# ProPrj_OASman_SMD_test_board_2_2025-03-0.net
KiCad netlist of a schematic drawn in EasyEDA Pro
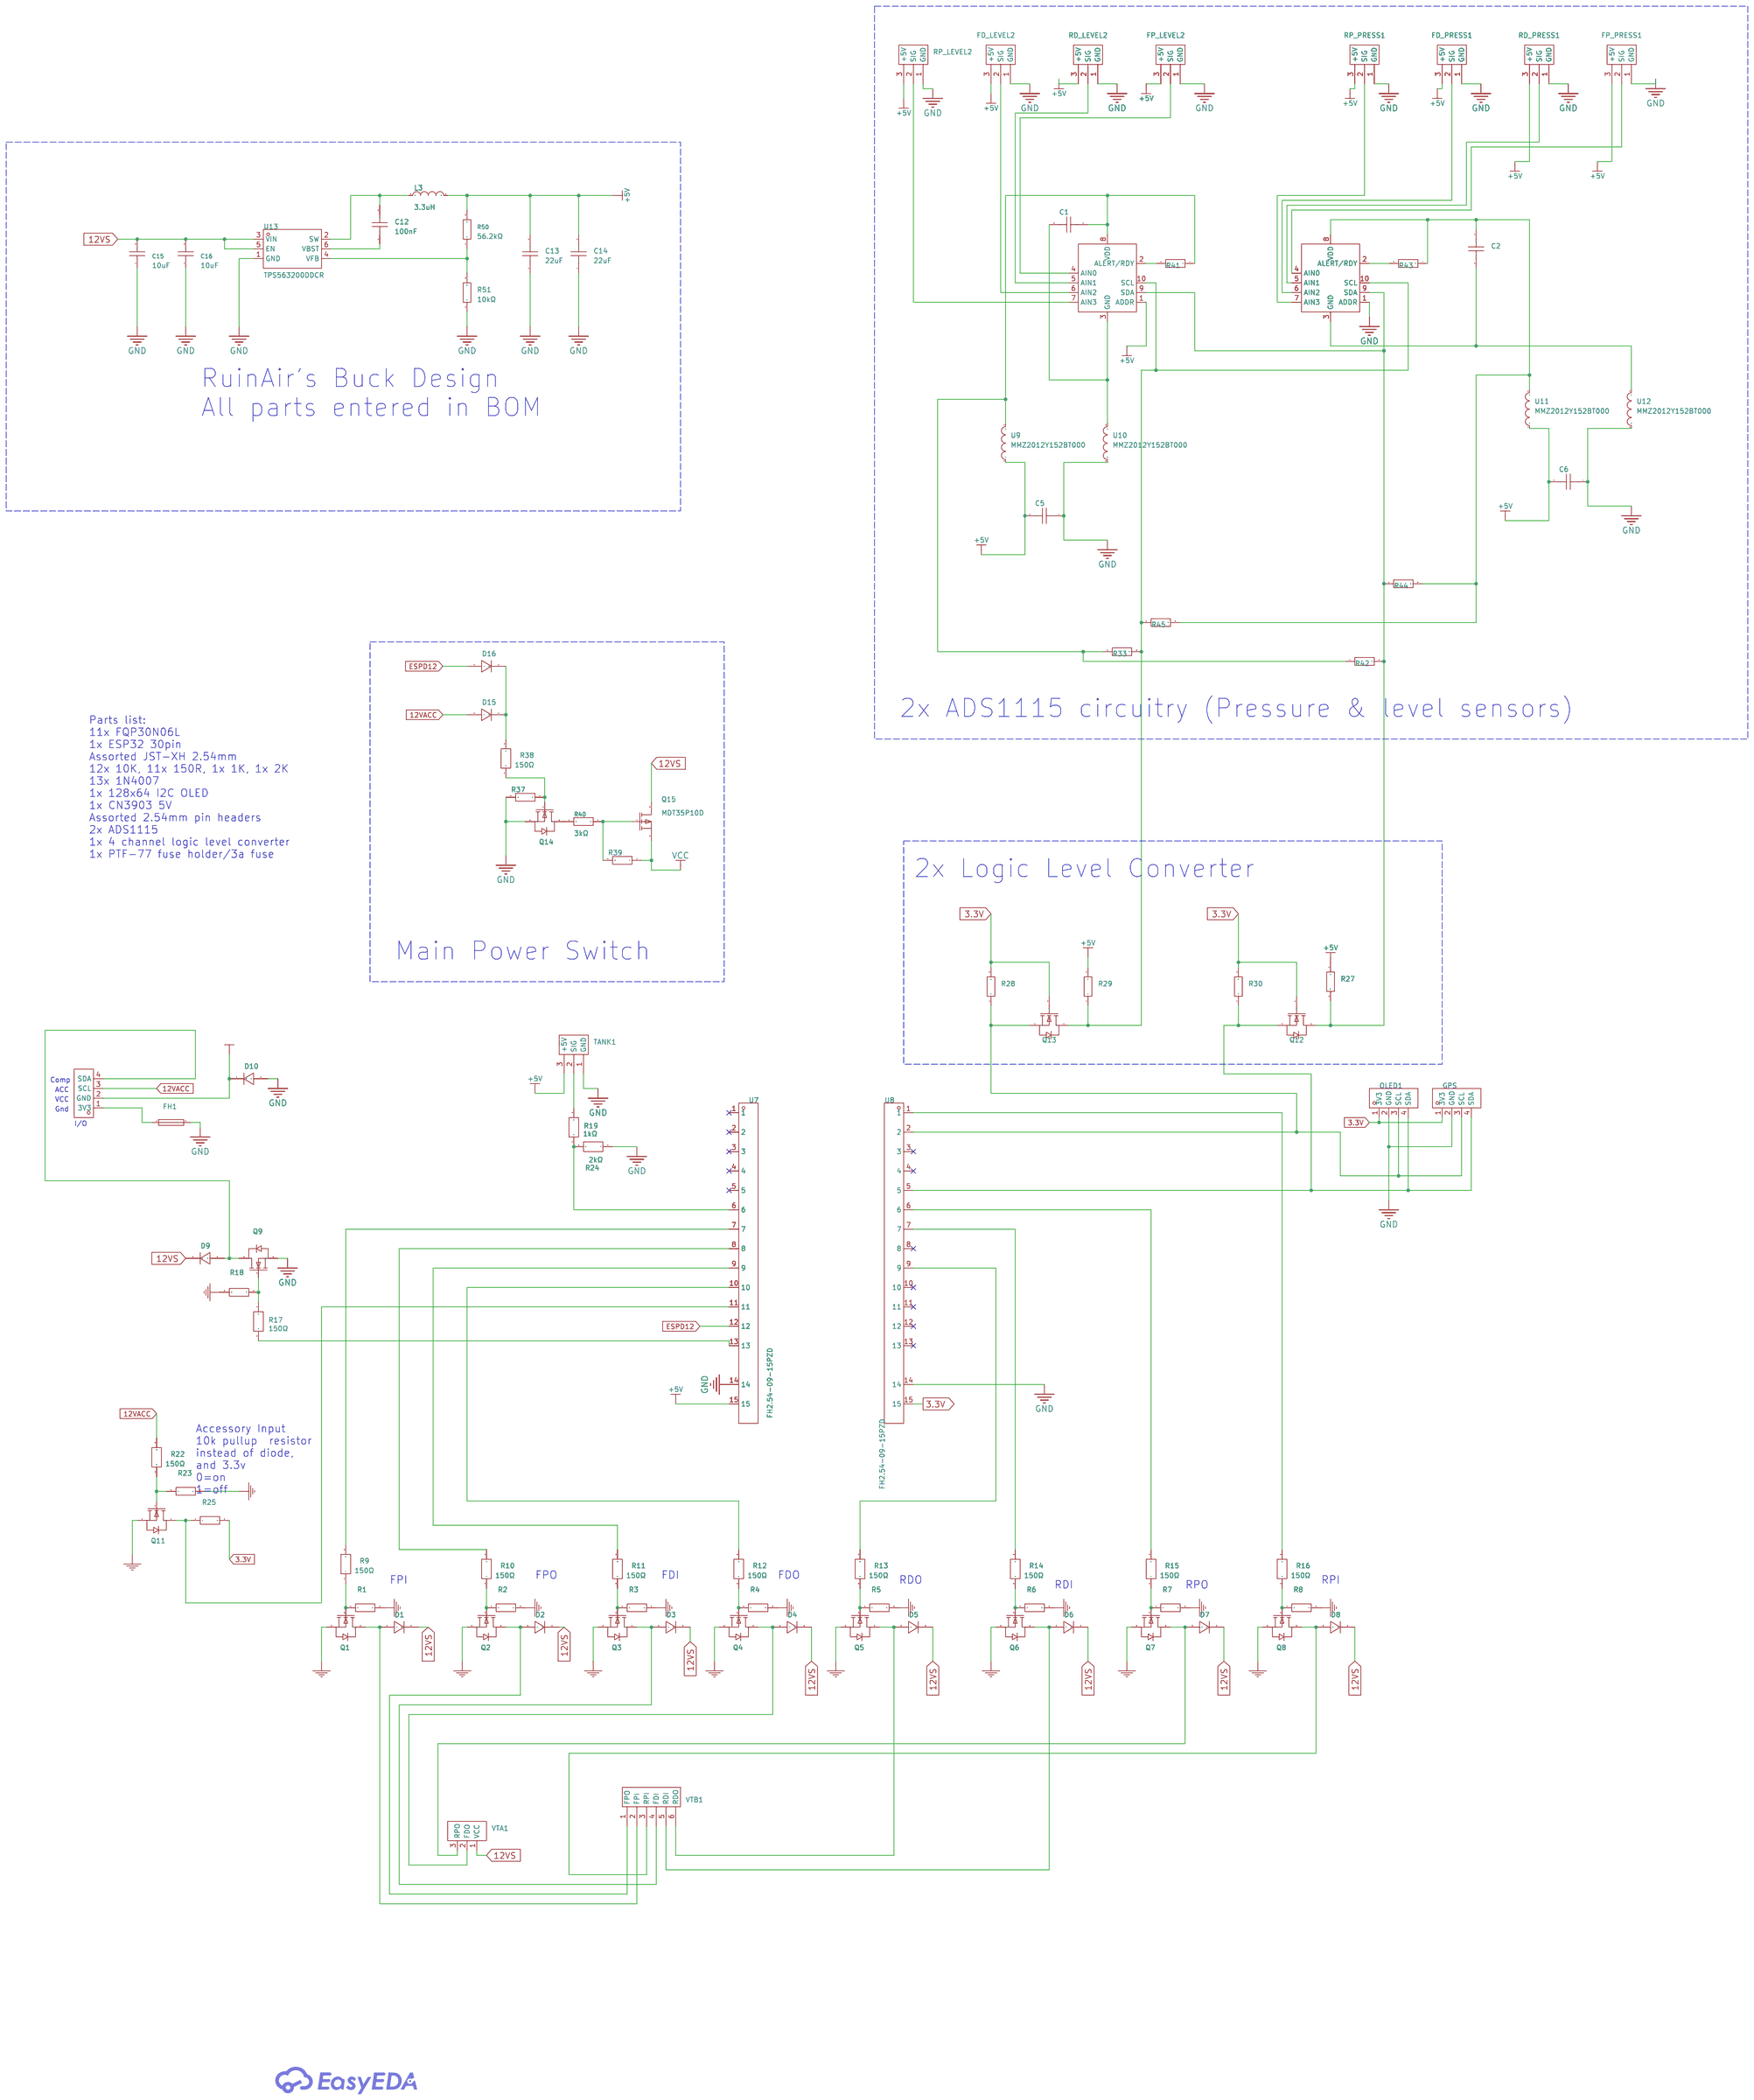
[diagram p0: schematic sheet]

(export (version "E")
  (design (tool "Eeschema 10.0.6"))
  (components
    (comp (ref "C1")
      (value "1uF")
      (footprint "easyedapro:C0603")
      (fields
        (field (name "Manufacturer Part") "GRM188R61H105KAALD")
        (field (name "Manufacturer") "muRata(村田)")
      )
      (libsource (lib "easyedapro") (part "GRM188R61H105KAALD"))
    )
    (comp (ref "C2")
      (value "1uF")
      (footprint "easyedapro:C0603")
      (fields
        (field (name "Manufacturer Part") "GRM188R61H105KAALD")
        (field (name "Manufacturer") "muRata(村田)")
      )
      (libsource (lib "easyedapro") (part "GRM188R61H105KAALD"))
    )
    (comp (ref "C5")
      (value "1uF")
      (footprint "easyedapro:C0603")
      (fields
        (field (name "Manufacturer Part") "GRM188R61H105KAALD")
        (field (name "Manufacturer") "muRata(村田)")
      )
      (libsource (lib "easyedapro") (part "GRM188R61H105KAALD"))
    )
    (comp (ref "C6")
      (value "1uF")
      (footprint "easyedapro:C0603")
      (fields
        (field (name "Manufacturer Part") "GRM188R61H105KAALD")
        (field (name "Manufacturer") "muRata(村田)")
      )
      (libsource (lib "easyedapro") (part "GRM188R61H105KAALD"))
    )
    (comp (ref "C12")
      (value "100nF")
      (footprint "easyedapro:C0402")
      (fields
        (field (name "Manufacturer Part") "CL05B104KB54PNC")
        (field (name "Manufacturer") "SAMSUNG(三星)")
      )
      (libsource (lib "easyedapro") (part "CL05B104KB54PNC"))
    )
    (comp (ref "C13")
      (value "22uF")
      (footprint "easyedapro:C0805")
      (fields
        (field (name "Manufacturer Part") "CL21A226MAQNNNE")
        (field (name "Manufacturer") "SAMSUNG(三星)")
      )
      (libsource (lib "easyedapro") (part "CL21A226MAQNNNE"))
    )
    (comp (ref "C14")
      (value "22uF")
      (footprint "easyedapro:C0805")
      (fields
        (field (name "Manufacturer Part") "CL21A226MAQNNNE")
        (field (name "Manufacturer") "SAMSUNG(三星)")
      )
      (libsource (lib "easyedapro") (part "CL21A226MAQNNNE"))
    )
    (comp (ref "C15")
      (value "10uF")
      (footprint "easyedapro:C1206")
      (fields
        (field (name "Manufacturer Part") "CL31A106KBHNNNE")
        (field (name "Manufacturer") "SAMSUNG(三星)")
      )
      (libsource (lib "easyedapro") (part "CL31A106KBHNNNE"))
    )
    (comp (ref "C16")
      (value "10uF")
      (footprint "easyedapro:C1206")
      (fields
        (field (name "Manufacturer Part") "CL31A106KBHNNNE")
        (field (name "Manufacturer") "SAMSUNG(三星)")
      )
      (libsource (lib "easyedapro") (part "CL31A106KBHNNNE"))
    )
    (comp (ref "CN1")
      (value "XH-4A绿色")
      (footprint "easyedapro:CONN-TH_XH-4A-1")
      (fields (field (name "Manufacturer") "BOOMELE(博穆精密)"))
      (libsource (lib "easyedapro") (part "XH-4A绿色"))
    )
    (comp (ref "D1")
      (value "SM4007PL")
      (footprint "easyedapro:SOD-123F_L2.8-W1.8-LS3.7-RD")
      (fields (field (name "Manufacturer") "MDD(辰达半导体)"))
      (libsource (lib "easyedapro") (part "SM4007PL"))
    )
    (comp (ref "D2")
      (value "SM4007PL")
      (footprint "easyedapro:SOD-123F_L2.8-W1.8-LS3.7-RD")
      (fields (field (name "Manufacturer") "MDD(辰达半导体)"))
      (libsource (lib "easyedapro") (part "SM4007PL"))
    )
    (comp (ref "D3")
      (value "SM4007PL")
      (footprint "easyedapro:SOD-123F_L2.8-W1.8-LS3.7-RD")
      (fields (field (name "Manufacturer") "MDD(辰达半导体)"))
      (libsource (lib "easyedapro") (part "SM4007PL"))
    )
    (comp (ref "D4")
      (value "SM4007PL")
      (footprint "easyedapro:SOD-123F_L2.8-W1.8-LS3.7-RD")
      (fields (field (name "Manufacturer") "MDD(辰达半导体)"))
      (libsource (lib "easyedapro") (part "SM4007PL"))
    )
    (comp (ref "D5")
      (value "SM4007PL")
      (footprint "easyedapro:SOD-123F_L2.8-W1.8-LS3.7-RD")
      (fields (field (name "Manufacturer") "MDD(辰达半导体)"))
      (libsource (lib "easyedapro") (part "SM4007PL"))
    )
    (comp (ref "D6")
      (value "SM4007PL")
      (footprint "easyedapro:SOD-123F_L2.8-W1.8-LS3.7-RD")
      (fields (field (name "Manufacturer") "MDD(辰达半导体)"))
      (libsource (lib "easyedapro") (part "SM4007PL"))
    )
    (comp (ref "D7")
      (value "SM4007PL")
      (footprint "easyedapro:SOD-123F_L2.8-W1.8-LS3.7-RD")
      (fields (field (name "Manufacturer") "MDD(辰达半导体)"))
      (libsource (lib "easyedapro") (part "SM4007PL"))
    )
    (comp (ref "D8")
      (value "SM4007PL")
      (footprint "easyedapro:SOD-123F_L2.8-W1.8-LS3.7-RD")
      (fields (field (name "Manufacturer") "MDD(辰达半导体)"))
      (libsource (lib "easyedapro") (part "SM4007PL"))
    )
    (comp (ref "D9")
      (value "SM4007PL")
      (footprint "easyedapro:SOD-123F_L2.8-W1.8-LS3.7-RD")
      (fields (field (name "Manufacturer") "MDD(辰达半导体)"))
      (libsource (lib "easyedapro") (part "SM4007PL"))
    )
    (comp (ref "D10")
      (value "SM4007PL")
      (footprint "easyedapro:SOD-123F_L2.8-W1.8-LS3.7-RD")
      (fields (field (name "Manufacturer") "MDD(辰达半导体)"))
      (libsource (lib "easyedapro") (part "SM4007PL"))
    )
    (comp (ref "D15")
      (value "SM4007PL")
      (footprint "easyedapro:SOD-123F_L2.8-W1.8-LS3.7-RD")
      (fields (field (name "Manufacturer") "MDD(辰达半导体)"))
      (libsource (lib "easyedapro") (part "SM4007PL"))
    )
    (comp (ref "D16")
      (value "SM4007PL")
      (footprint "easyedapro:SOD-123F_L2.8-W1.8-LS3.7-RD")
      (fields (field (name "Manufacturer") "MDD(辰达半导体)"))
      (libsource (lib "easyedapro") (part "SM4007PL"))
    )
    (comp (ref "FD_LEVEL2")
      (value "XH-3A")
      (footprint "easyedapro:CONN-TH_XH-3A")
      (fields (field (name "Manufacturer") "BOOMELE(博穆精密)"))
      (libsource (lib "easyedapro") (part "XH-3A"))
    )
    (comp (ref "FD_PRESS1")
      (value "XH-3A")
      (footprint "easyedapro:CONN-TH_XH-3A")
      (fields (field (name "Manufacturer") "BOOMELE(博穆精密)"))
      (libsource (lib "easyedapro") (part "XH-3A"))
    )
    (comp (ref "FH1")
      (value "PTF-77")
      (description "Fuseholder Type:- Voltage Rating:250V Current Rating:10A Fuse Type:- Fuse Size:-")
      (libsource (lib "easyedapro") (part "PTF-77"))
    )
    (comp (ref "FP_LEVEL2")
      (value "XH-3A")
      (footprint "easyedapro:CONN-TH_XH-3A")
      (fields (field (name "Manufacturer") "BOOMELE(博穆精密)"))
      (libsource (lib "easyedapro") (part "XH-3A"))
    )
    (comp (ref "FP_PRESS1")
      (value "XH-3A")
      (footprint "easyedapro:CONN-TH_XH-3A")
      (fields (field (name "Manufacturer") "BOOMELE(博穆精密)"))
      (libsource (lib "easyedapro") (part "XH-3A"))
    )
    (comp (ref "GPS")
      (value "XH-4A绿色")
      (footprint "easyedapro:CONN-TH_XH-4A-1")
      (fields (field (name "Manufacturer") "BOOMELE(博穆精密)"))
      (libsource (lib "easyedapro") (part "XH-4A绿色"))
    )
    (comp (ref "L3")
      (value "3.3uH")
      (footprint "easyedapro:IND-SMD_L4.5-W4.1_SL0420")
      (description "Inductance: Tolerance:±20% Tolerance:±20% Rated Current: Saturation Current (Isat):4A")
      (fields (field (name "Manufacturer Part") "SL0420-3R3M") (field (name "Manufacturer") "台湾陆海"))
      (libsource (lib "easyedapro") (part "SL0420-3R3M"))
    )
    (comp (ref "OLED1")
      (value "XH-4A绿色")
      (footprint "easyedapro:CONN-TH_XH-4A-1")
      (fields (field (name "Manufacturer") "BOOMELE(博穆精密)"))
      (libsource (lib "easyedapro") (part "XH-4A绿色"))
    )
    (comp (ref "Q1") (value "MDT30N06L") (libsource (lib "easyedapro") (part "FQP30N06L")))
    (comp (ref "Q2") (value "MDT30N06L") (libsource (lib "easyedapro") (part "FQP30N06L")))
    (comp (ref "Q3") (value "MDT30N06L") (libsource (lib "easyedapro") (part "FQP30N06L")))
    (comp (ref "Q4") (value "MDT30N06L") (libsource (lib "easyedapro") (part "FQP30N06L")))
    (comp (ref "Q5") (value "MDT30N06L") (libsource (lib "easyedapro") (part "FQP30N06L")))
    (comp (ref "Q6") (value "MDT30N06L") (libsource (lib "easyedapro") (part "FQP30N06L")))
    (comp (ref "Q7") (value "MDT30N06L") (libsource (lib "easyedapro") (part "FQP30N06L")))
    (comp (ref "Q8") (value "MDT30N06L") (libsource (lib "easyedapro") (part "FQP30N06L")))
    (comp (ref "Q9") (value "MDT30N06L") (libsource (lib "easyedapro") (part "FQP30N06L")))
    (comp (ref "Q11") (value "MDT30N06L") (libsource (lib "easyedapro") (part "FQP30N06L")))
    (comp (ref "Q12")
      (value "BSS138")
      (footprint "easyedapro:SOT-23-3_L2.9-W1.6-P1.90-LS2.8-BR")
      (fields (field (name "Manufacturer") "SHIKUES(时科)"))
      (libsource (lib "easyedapro") (part "BSS138_C112239"))
    )
    (comp (ref "Q13")
      (value "BSS138")
      (footprint "easyedapro:SOT-23-3_L2.9-W1.6-P1.90-LS2.8-BR")
      (fields (field (name "Manufacturer") "SHIKUES(时科)"))
      (libsource (lib "easyedapro") (part "BSS138_C112239"))
    )
    (comp (ref "Q14") (value "MDT30N06L") (libsource (lib "easyedapro") (part "FQP30N06L")))
    (comp (ref "Q15")
      (value "MDT35P10D")
      (footprint "easyedapro:TO-252-2_L6.6-W6.1-P4.57-LS9.9-BR-CW")
      (fields (field (name "Manufacturer") "minos(迈诺斯)"))
      (libsource (lib "easyedapro") (part "MDT35P10D"))
    )
    (comp (ref "R1")
      (value "10kΩ")
      (footprint "easyedapro:R1206")
      (fields
        (field (name "Manufacturer Part") "1206W4F1002T5E")
        (field (name "Manufacturer") "UNI-ROYAL(厚声)")
      )
      (libsource (lib "easyedapro") (part "1206W4F1002T5E"))
    )
    (comp (ref "R2")
      (value "10kΩ")
      (footprint "easyedapro:R1206")
      (fields
        (field (name "Manufacturer Part") "1206W4F1002T5E")
        (field (name "Manufacturer") "UNI-ROYAL(厚声)")
      )
      (libsource (lib "easyedapro") (part "1206W4F1002T5E"))
    )
    (comp (ref "R3")
      (value "10kΩ")
      (footprint "easyedapro:R1206")
      (fields
        (field (name "Manufacturer Part") "1206W4F1002T5E")
        (field (name "Manufacturer") "UNI-ROYAL(厚声)")
      )
      (libsource (lib "easyedapro") (part "1206W4F1002T5E"))
    )
    (comp (ref "R4")
      (value "10kΩ")
      (footprint "easyedapro:R1206")
      (fields
        (field (name "Manufacturer Part") "1206W4F1002T5E")
        (field (name "Manufacturer") "UNI-ROYAL(厚声)")
      )
      (libsource (lib "easyedapro") (part "1206W4F1002T5E"))
    )
    (comp (ref "R5")
      (value "10kΩ")
      (footprint "easyedapro:R1206")
      (fields
        (field (name "Manufacturer Part") "1206W4F1002T5E")
        (field (name "Manufacturer") "UNI-ROYAL(厚声)")
      )
      (libsource (lib "easyedapro") (part "1206W4F1002T5E"))
    )
    (comp (ref "R6")
      (value "10kΩ")
      (footprint "easyedapro:R1206")
      (fields
        (field (name "Manufacturer Part") "1206W4F1002T5E")
        (field (name "Manufacturer") "UNI-ROYAL(厚声)")
      )
      (libsource (lib "easyedapro") (part "1206W4F1002T5E"))
    )
    (comp (ref "R7")
      (value "10kΩ")
      (footprint "easyedapro:R1206")
      (fields
        (field (name "Manufacturer Part") "1206W4F1002T5E")
        (field (name "Manufacturer") "UNI-ROYAL(厚声)")
      )
      (libsource (lib "easyedapro") (part "1206W4F1002T5E"))
    )
    (comp (ref "R8")
      (value "10kΩ")
      (footprint "easyedapro:R1206")
      (fields
        (field (name "Manufacturer Part") "1206W4F1002T5E")
        (field (name "Manufacturer") "UNI-ROYAL(厚声)")
      )
      (libsource (lib "easyedapro") (part "1206W4F1002T5E"))
    )
    (comp (ref "R9")
      (value "150Ω")
      (footprint "easyedapro:R1206")
      (fields (field (name "Manufacturer Part") "FRC1206J151 TS") (field (name "Manufacturer") "FOJAN(富捷)"))
      (libsource (lib "easyedapro") (part "FRC1206J151 TS"))
    )
    (comp (ref "R10")
      (value "150Ω")
      (footprint "easyedapro:R1206")
      (fields (field (name "Manufacturer Part") "FRC1206J151 TS") (field (name "Manufacturer") "FOJAN(富捷)"))
      (libsource (lib "easyedapro") (part "FRC1206J151 TS"))
    )
    (comp (ref "R11")
      (value "150Ω")
      (footprint "easyedapro:R1206")
      (fields (field (name "Manufacturer Part") "FRC1206J151 TS") (field (name "Manufacturer") "FOJAN(富捷)"))
      (libsource (lib "easyedapro") (part "FRC1206J151 TS"))
    )
    (comp (ref "R12")
      (value "150Ω")
      (footprint "easyedapro:R1206")
      (fields (field (name "Manufacturer Part") "FRC1206J151 TS") (field (name "Manufacturer") "FOJAN(富捷)"))
      (libsource (lib "easyedapro") (part "FRC1206J151 TS"))
    )
    (comp (ref "R13")
      (value "150Ω")
      (footprint "easyedapro:R1206")
      (fields (field (name "Manufacturer Part") "FRC1206J151 TS") (field (name "Manufacturer") "FOJAN(富捷)"))
      (libsource (lib "easyedapro") (part "FRC1206J151 TS"))
    )
    (comp (ref "R14")
      (value "150Ω")
      (footprint "easyedapro:R1206")
      (fields (field (name "Manufacturer Part") "FRC1206J151 TS") (field (name "Manufacturer") "FOJAN(富捷)"))
      (libsource (lib "easyedapro") (part "FRC1206J151 TS"))
    )
    (comp (ref "R15")
      (value "150Ω")
      (footprint "easyedapro:R1206")
      (fields (field (name "Manufacturer Part") "FRC1206J151 TS") (field (name "Manufacturer") "FOJAN(富捷)"))
      (libsource (lib "easyedapro") (part "FRC1206J151 TS"))
    )
    (comp (ref "R16")
      (value "150Ω")
      (footprint "easyedapro:R1206")
      (fields (field (name "Manufacturer Part") "FRC1206J151 TS") (field (name "Manufacturer") "FOJAN(富捷)"))
      (libsource (lib "easyedapro") (part "FRC1206J151 TS"))
    )
    (comp (ref "R17")
      (value "150Ω")
      (footprint "easyedapro:R1206")
      (fields (field (name "Manufacturer Part") "FRC1206J151 TS") (field (name "Manufacturer") "FOJAN(富捷)"))
      (libsource (lib "easyedapro") (part "FRC1206J151 TS"))
    )
    (comp (ref "R18")
      (value "10kΩ")
      (footprint "easyedapro:R1206")
      (fields
        (field (name "Manufacturer Part") "1206W4F1002T5E")
        (field (name "Manufacturer") "UNI-ROYAL(厚声)")
      )
      (libsource (lib "easyedapro") (part "1206W4F1002T5E"))
    )
    (comp (ref "R19")
      (value "1kΩ")
      (footprint "easyedapro:R1206")
      (fields (field (name "Manufacturer Part") "FRC1206J102 TS") (field (name "Manufacturer") "FOJAN(富捷)"))
      (libsource (lib "easyedapro") (part "FRC1206J102 TS"))
    )
    (comp (ref "R22")
      (value "150Ω")
      (footprint "easyedapro:R1206")
      (fields (field (name "Manufacturer Part") "FRC1206J151 TS") (field (name "Manufacturer") "FOJAN(富捷)"))
      (libsource (lib "easyedapro") (part "FRC1206J151 TS"))
    )
    (comp (ref "R23")
      (value "10kΩ")
      (footprint "easyedapro:R1206")
      (fields
        (field (name "Manufacturer Part") "1206W4F1002T5E")
        (field (name "Manufacturer") "UNI-ROYAL(厚声)")
      )
      (libsource (lib "easyedapro") (part "1206W4F1002T5E"))
    )
    (comp (ref "R24")
      (value "2kΩ")
      (footprint "easyedapro:R1206")
      (fields (field (name "Manufacturer Part") "FRC1206J202 TS") (field (name "Manufacturer") "FOJAN(富捷)"))
      (libsource (lib "easyedapro") (part "FRC1206J202 TS"))
    )
    (comp (ref "R25")
      (value "10kΩ")
      (footprint "easyedapro:R1206")
      (fields
        (field (name "Manufacturer Part") "1206W4F1002T5E")
        (field (name "Manufacturer") "UNI-ROYAL(厚声)")
      )
      (libsource (lib "easyedapro") (part "1206W4F1002T5E"))
    )
    (comp (ref "R27")
      (value "10kΩ")
      (footprint "easyedapro:R1206")
      (fields
        (field (name "Manufacturer Part") "1206W4F1002T5E")
        (field (name "Manufacturer") "UNI-ROYAL(厚声)")
      )
      (libsource (lib "easyedapro") (part "1206W4F1002T5E"))
    )
    (comp (ref "R28")
      (value "10kΩ")
      (footprint "easyedapro:R1206")
      (fields
        (field (name "Manufacturer Part") "1206W4F1002T5E")
        (field (name "Manufacturer") "UNI-ROYAL(厚声)")
      )
      (libsource (lib "easyedapro") (part "1206W4F1002T5E"))
    )
    (comp (ref "R29")
      (value "10kΩ")
      (footprint "easyedapro:R1206")
      (fields
        (field (name "Manufacturer Part") "1206W4F1002T5E")
        (field (name "Manufacturer") "UNI-ROYAL(厚声)")
      )
      (libsource (lib "easyedapro") (part "1206W4F1002T5E"))
    )
    (comp (ref "R30")
      (value "10kΩ")
      (footprint "easyedapro:R1206")
      (fields
        (field (name "Manufacturer Part") "1206W4F1002T5E")
        (field (name "Manufacturer") "UNI-ROYAL(厚声)")
      )
      (libsource (lib "easyedapro") (part "1206W4F1002T5E"))
    )
    (comp (ref "R33")
      (value "1MΩ")
      (footprint "easyedapro:R1206")
      (fields
        (field (name "Manufacturer Part") "1206W4F1004T5E")
        (field (name "Manufacturer") "UNI-ROYAL(厚声)")
      )
      (libsource (lib "easyedapro") (part "1206W4F1004T5E"))
    )
    (comp (ref "R37")
      (value "10kΩ")
      (footprint "easyedapro:R1206")
      (fields
        (field (name "Manufacturer Part") "1206W4F1002T5E")
        (field (name "Manufacturer") "UNI-ROYAL(厚声)")
      )
      (libsource (lib "easyedapro") (part "1206W4F1002T5E"))
    )
    (comp (ref "R38")
      (value "150Ω")
      (footprint "easyedapro:R1206")
      (fields (field (name "Manufacturer Part") "FRC1206J151 TS") (field (name "Manufacturer") "FOJAN(富捷)"))
      (libsource (lib "easyedapro") (part "FRC1206J151 TS"))
    )
    (comp (ref "R39")
      (value "10kΩ")
      (footprint "easyedapro:R1206")
      (fields
        (field (name "Manufacturer Part") "1206W4F1002T5E")
        (field (name "Manufacturer") "UNI-ROYAL(厚声)")
      )
      (libsource (lib "easyedapro") (part "1206W4F1002T5E"))
    )
    (comp (ref "R40")
      (value "3kΩ")
      (footprint "easyedapro:R1206")
      (fields
        (field (name "Manufacturer Part") "1206W4F3001T5E")
        (field (name "Manufacturer") "UNI-ROYAL(厚声)")
      )
      (libsource (lib "easyedapro") (part "1206W4F3001T5E"))
    )
    (comp (ref "R41")
      (value "1MΩ")
      (footprint "easyedapro:R1206")
      (fields
        (field (name "Manufacturer Part") "1206W4F1004T5E")
        (field (name "Manufacturer") "UNI-ROYAL(厚声)")
      )
      (libsource (lib "easyedapro") (part "1206W4F1004T5E"))
    )
    (comp (ref "R42")
      (value "1MΩ")
      (footprint "easyedapro:R1206")
      (fields
        (field (name "Manufacturer Part") "1206W4F1004T5E")
        (field (name "Manufacturer") "UNI-ROYAL(厚声)")
      )
      (libsource (lib "easyedapro") (part "1206W4F1004T5E"))
    )
    (comp (ref "R43")
      (value "1MΩ")
      (footprint "easyedapro:R1206")
      (fields
        (field (name "Manufacturer Part") "1206W4F1004T5E")
        (field (name "Manufacturer") "UNI-ROYAL(厚声)")
      )
      (libsource (lib "easyedapro") (part "1206W4F1004T5E"))
    )
    (comp (ref "R44")
      (value "1MΩ")
      (footprint "easyedapro:R1206")
      (fields
        (field (name "Manufacturer Part") "1206W4F1004T5E")
        (field (name "Manufacturer") "UNI-ROYAL(厚声)")
      )
      (libsource (lib "easyedapro") (part "1206W4F1004T5E"))
    )
    (comp (ref "R45")
      (value "1MΩ")
      (footprint "easyedapro:R1206")
      (fields
        (field (name "Manufacturer Part") "1206W4F1004T5E")
        (field (name "Manufacturer") "UNI-ROYAL(厚声)")
      )
      (libsource (lib "easyedapro") (part "1206W4F1004T5E"))
    )
    (comp (ref "R50")
      (value "56.2kΩ")
      (footprint "easyedapro:R0402")
      (fields
        (field (name "Manufacturer Part") "0402WGF5622TCE")
        (field (name "Manufacturer") "UNI-ROYAL(厚声)")
      )
      (libsource (lib "easyedapro") (part "0402WGF5622TCE"))
    )
    (comp (ref "R51")
      (value "10kΩ")
      (footprint "easyedapro:R0402")
      (fields
        (field (name "Manufacturer Part") "0402WGF1002TCE")
        (field (name "Manufacturer") "UNI-ROYAL(厚声)")
      )
      (libsource (lib "easyedapro") (part "0402WGF1002TCE"))
    )
    (comp (ref "RD_LEVEL2")
      (value "XH-3A")
      (footprint "easyedapro:CONN-TH_XH-3A")
      (fields (field (name "Manufacturer") "BOOMELE(博穆精密)"))
      (libsource (lib "easyedapro") (part "XH-3A"))
    )
    (comp (ref "RD_PRESS1")
      (value "XH-3A")
      (footprint "easyedapro:CONN-TH_XH-3A")
      (fields (field (name "Manufacturer") "BOOMELE(博穆精密)"))
      (libsource (lib "easyedapro") (part "XH-3A"))
    )
    (comp (ref "RP_LEVEL2")
      (value "XH-3A")
      (footprint "easyedapro:CONN-TH_XH-3A")
      (fields (field (name "Manufacturer") "BOOMELE(博穆精密)"))
      (libsource (lib "easyedapro") (part "XH-3A"))
    )
    (comp (ref "RP_PRESS1")
      (value "XH-3A")
      (footprint "easyedapro:CONN-TH_XH-3A")
      (fields (field (name "Manufacturer") "BOOMELE(博穆精密)"))
      (libsource (lib "easyedapro") (part "XH-3A"))
    )
    (comp (ref "TANK1")
      (value "XH-3A")
      (footprint "easyedapro:CONN-TH_XH-3A")
      (fields (field (name "Manufacturer") "BOOMELE(博穆精密)"))
      (libsource (lib "easyedapro") (part "XH-3A"))
    )
    (comp (ref "U4")
      (value "ADS1115IDGSR")
      (fields (field (name "Manufacturer") "TI(德州仪器)"))
      (libsource (lib "easyedapro") (part "Analog_ADC_ADS1115IDGS"))
    )
    (comp (ref "U5")
      (value "ADS1115IDGSR")
      (fields (field (name "Manufacturer") "TI(德州仪器)"))
      (libsource (lib "easyedapro") (part "Analog_ADC_ADS1115IDGS"))
    )
    (comp (ref "U7")
      (value "FH2.54-09-15PZD")
      (footprint "easyedapro:HDR-TH_15P-P2.54-V-F-1")
      (fields (field (name "Manufacturer") "XUNPU(讯普)"))
      (libsource (lib "easyedapro") (part "FH2.54-09-15PZD"))
    )
    (comp (ref "U8")
      (value "FH2.54-09-15PZD")
      (footprint "easyedapro:HDR-TH_15P-P2.54-V-F-1")
      (fields (field (name "Manufacturer") "XUNPU(讯普)"))
      (libsource (lib "easyedapro") (part "FH2.54-09-15PZD"))
    )
    (comp (ref "U9")
      (value "MMZ2012Y152BT000")
      (footprint "easyedapro:L0805")
      (fields (field (name "Manufacturer") "TDK"))
      (libsource (lib "easyedapro") (part "MMZ2012Y152BT000"))
    )
    (comp (ref "U10")
      (value "MMZ2012Y152BT000")
      (footprint "easyedapro:L0805")
      (fields (field (name "Manufacturer") "TDK"))
      (libsource (lib "easyedapro") (part "MMZ2012Y152BT000"))
    )
    (comp (ref "U11")
      (value "MMZ2012Y152BT000")
      (footprint "easyedapro:L0805")
      (fields (field (name "Manufacturer") "TDK"))
      (libsource (lib "easyedapro") (part "MMZ2012Y152BT000"))
    )
    (comp (ref "U12")
      (value "MMZ2012Y152BT000")
      (footprint "easyedapro:L0805")
      (fields (field (name "Manufacturer") "TDK"))
      (libsource (lib "easyedapro") (part "MMZ2012Y152BT000"))
    )
    (comp (ref "U13")
      (value "TPS563200DDCR")
      (footprint "easyedapro:SOT-23-6_L2.9-W1.6-P0.95-LS2.8-BR")
      (fields (field (name "Manufacturer") "TI(德州仪器)"))
      (libsource (lib "easyedapro") (part "TPS563200DDCR"))
    )
    (comp (ref "VTA1") (value "XH-3A") (libsource (lib "easyedapro") (part "Valvetable A")))
    (comp (ref "VTB1")
      (value "XH-6A")
      (footprint "easyedapro:CONN-TH_6P-P2.50_XH-6A")
      (fields (field (name "Manufacturer") "BOOMELE(博穆精密)"))
      (libsource (lib "easyedapro") (part "XH-6A"))
    )
  )
  (nets
    (net (code "1") (name "+5V") (class "Default")
      (node (ref "C13") (pin "2") (pinfunction "2_2") (pintype "unspecified"))
      (node (ref "C14") (pin "2") (pinfunction "2_2") (pintype "unspecified"))
      (node (ref "C5") (pin "2") (pinfunction "2_2") (pintype "unspecified"))
      (node (ref "C6") (pin "2") (pinfunction "2_2") (pintype "unspecified"))
      (node (ref "FD_LEVEL2") (pin "3") (pinfunction "+5V_3") (pintype "input"))
      (node (ref "FD_PRESS1") (pin "3") (pinfunction "+5V_3") (pintype "input"))
      (node (ref "FP_LEVEL2") (pin "3") (pinfunction "+5V_3") (pintype "input"))
      (node (ref "FP_PRESS1") (pin "3") (pinfunction "+5V_3") (pintype "input"))
      (node (ref "L3") (pin "2") (pinfunction "2_2") (pintype "unspecified"))
      (node (ref "R27") (pin "1") (pinfunction "1_1") (pintype "input"))
      (node (ref "R29") (pin "2") (pinfunction "2_2") (pintype "input"))
      (node (ref "R50") (pin "2") (pinfunction "2_2") (pintype "input"))
      (node (ref "RD_LEVEL2") (pin "3") (pinfunction "+5V_3") (pintype "input"))
      (node (ref "RD_PRESS1") (pin "3") (pinfunction "+5V_3") (pintype "input"))
      (node (ref "RP_LEVEL2") (pin "3") (pinfunction "+5V_3") (pintype "input"))
      (node (ref "RP_PRESS1") (pin "3") (pinfunction "+5V_3") (pintype "input"))
      (node (ref "TANK1") (pin "3") (pinfunction "+5V_3") (pintype "input"))
      (node (ref "U11") (pin "1") (pinfunction "1_1") (pintype "input"))
      (node (ref "U4") (pin "1") (pinfunction "ADDR_1") (pintype "input"))
      (node (ref "U7") (pin "15") (pinfunction "15_15") (pintype "unspecified"))
      (node (ref "U9") (pin "1") (pinfunction "1_1") (pintype "input"))
    )
    (net (code "2") (name "3.3V") (class "Default")
      (node (ref "GPS") (pin "1") (pinfunction "3V3_1") (pintype "input"))
      (node (ref "OLED1") (pin "1") (pinfunction "3V3_1") (pintype "input"))
      (node (ref "Q12") (pin "1") (pinfunction "G_1") (pintype "unspecified"))
      (node (ref "Q13") (pin "1") (pinfunction "G_1") (pintype "unspecified"))
      (node (ref "R25") (pin "2") (pinfunction "2_2") (pintype "input"))
      (node (ref "R28") (pin "2") (pinfunction "2_2") (pintype "input"))
      (node (ref "R30") (pin "2") (pinfunction "2_2") (pintype "input"))
      (node (ref "U8") (pin "15") (pinfunction "15_15") (pintype "unspecified"))
    )
    (net (code "3") (name "12VACC") (class "Default")
      (node (ref "CN1") (pin "3") (pinfunction "SCL_3") (pintype "input"))
      (node (ref "D15") (pin "2") (pinfunction "A_2") (pintype "unspecified"))
      (node (ref "R22") (pin "2") (pinfunction "2_2") (pintype "unspecified"))
    )
    (net (code "4") (name "12VS") (class "Default")
      (node (ref "C15") (pin "2") (pinfunction "2_2") (pintype "input"))
      (node (ref "C16") (pin "2") (pinfunction "2_2") (pintype "input"))
      (node (ref "D1") (pin "1") (pinfunction "C_1") (pintype "unspecified"))
      (node (ref "D2") (pin "1") (pinfunction "C_1") (pintype "unspecified"))
      (node (ref "D3") (pin "1") (pinfunction "C_1") (pintype "unspecified"))
      (node (ref "D4") (pin "1") (pinfunction "C_1") (pintype "unspecified"))
      (node (ref "D5") (pin "1") (pinfunction "C_1") (pintype "unspecified"))
      (node (ref "D6") (pin "1") (pinfunction "C_1") (pintype "unspecified"))
      (node (ref "D7") (pin "1") (pinfunction "C_1") (pintype "unspecified"))
      (node (ref "D8") (pin "1") (pinfunction "C_1") (pintype "unspecified"))
      (node (ref "D9") (pin "1") (pinfunction "C_1") (pintype "unspecified"))
      (node (ref "Q15") (pin "2") (pinfunction "D_2") (pintype "unspecified"))
      (node (ref "U13") (pin "3") (pinfunction "VIN_3") (pintype "unspecified"))
      (node (ref "U13") (pin "5") (pinfunction "EN_5") (pintype "unspecified"))
      (node (ref "VTA1") (pin "1") (pinfunction "VCC_1") (pintype "unspecified"))
    )
    (net (code "5") (name "ESPD12") (class "Default")
      (node (ref "D16") (pin "2") (pinfunction "A_2") (pintype "unspecified"))
      (node (ref "U7") (pin "12") (pinfunction "12_12") (pintype "unspecified"))
    )
    (net (code "6") (name "GND") (class "Default")
      (node (ref "C13") (pin "1") (pinfunction "1_1") (pintype "unspecified"))
      (node (ref "C14") (pin "1") (pinfunction "1_1") (pintype "unspecified"))
      (node (ref "C15") (pin "1") (pinfunction "1_1") (pintype "input"))
      (node (ref "C16") (pin "1") (pinfunction "1_1") (pintype "input"))
      (node (ref "C5") (pin "1") (pinfunction "1_1") (pintype "unspecified"))
      (node (ref "C6") (pin "1") (pinfunction "1_1") (pintype "unspecified"))
      (node (ref "D10") (pin "2") (pinfunction "A_2") (pintype "unspecified"))
      (node (ref "FD_LEVEL2") (pin "1") (pinfunction "GND_1") (pintype "input"))
      (node (ref "FD_PRESS1") (pin "1") (pinfunction "GND_1") (pintype "input"))
      (node (ref "FH1") (pin "2") (pinfunction "2_2") (pintype "unspecified"))
      (node (ref "FP_LEVEL2") (pin "1") (pinfunction "GND_1") (pintype "input"))
      (node (ref "FP_PRESS1") (pin "1") (pinfunction "GND_1") (pintype "input"))
      (node (ref "GPS") (pin "2") (pinfunction "GND_2") (pintype "input"))
      (node (ref "OLED1") (pin "2") (pinfunction "GND_2") (pintype "input"))
      (node (ref "Q1") (pin "3") (pinfunction "S_3") (pintype "unspecified"))
      (node (ref "Q11") (pin "3") (pinfunction "S_3") (pintype "unspecified"))
      (node (ref "Q14") (pin "3") (pinfunction "S_3") (pintype "unspecified"))
      (node (ref "Q2") (pin "3") (pinfunction "S_3") (pintype "unspecified"))
      (node (ref "Q3") (pin "3") (pinfunction "S_3") (pintype "unspecified"))
      (node (ref "Q4") (pin "3") (pinfunction "S_3") (pintype "unspecified"))
      (node (ref "Q5") (pin "3") (pinfunction "S_3") (pintype "unspecified"))
      (node (ref "Q6") (pin "3") (pinfunction "S_3") (pintype "unspecified"))
      (node (ref "Q7") (pin "3") (pinfunction "S_3") (pintype "unspecified"))
      (node (ref "Q8") (pin "3") (pinfunction "S_3") (pintype "unspecified"))
      (node (ref "Q9") (pin "3") (pinfunction "S_3") (pintype "unspecified"))
      (node (ref "R1") (pin "2") (pinfunction "2_2") (pintype "input"))
      (node (ref "R18") (pin "2") (pinfunction "2_2") (pintype "input"))
      (node (ref "R2") (pin "2") (pinfunction "2_2") (pintype "input"))
      (node (ref "R23") (pin "2") (pinfunction "2_2") (pintype "input"))
      (node (ref "R24") (pin "1") (pinfunction "1_1") (pintype "unspecified"))
      (node (ref "R3") (pin "2") (pinfunction "2_2") (pintype "input"))
      (node (ref "R37") (pin "2") (pinfunction "2_2") (pintype "input"))
      (node (ref "R4") (pin "2") (pinfunction "2_2") (pintype "input"))
      (node (ref "R5") (pin "2") (pinfunction "2_2") (pintype "input"))
      (node (ref "R51") (pin "1") (pinfunction "1_1") (pintype "input"))
      (node (ref "R6") (pin "2") (pinfunction "2_2") (pintype "input"))
      (node (ref "R7") (pin "2") (pinfunction "2_2") (pintype "input"))
      (node (ref "R8") (pin "2") (pinfunction "2_2") (pintype "input"))
      (node (ref "RD_LEVEL2") (pin "1") (pinfunction "GND_1") (pintype "input"))
      (node (ref "RD_PRESS1") (pin "1") (pinfunction "GND_1") (pintype "input"))
      (node (ref "RP_LEVEL2") (pin "1") (pinfunction "GND_1") (pintype "input"))
      (node (ref "RP_PRESS1") (pin "1") (pinfunction "GND_1") (pintype "input"))
      (node (ref "TANK1") (pin "1") (pinfunction "GND_1") (pintype "input"))
      (node (ref "U10") (pin "1") (pinfunction "1_1") (pintype "input"))
      (node (ref "U12") (pin "1") (pinfunction "1_1") (pintype "input"))
      (node (ref "U13") (pin "1") (pinfunction "GND_1") (pintype "unspecified"))
      (node (ref "U5") (pin "1") (pinfunction "ADDR_1") (pintype "input"))
      (node (ref "U7") (pin "14") (pinfunction "14_14") (pintype "unspecified"))
      (node (ref "U8") (pin "14") (pinfunction "14_14") (pintype "unspecified"))
    )
    (net (code "7") (name "Net-(CN1-3V3)") (class "Default")
      (node (ref "CN1") (pin "1") (pinfunction "3V3_1") (pintype "input"))
      (node (ref "FH1") (pin "1") (pinfunction "1_1") (pintype "unspecified"))
    )
    (net (code "8") (name "Net-(CN1-SDA)") (class "Default")
      (node (ref "CN1") (pin "4") (pinfunction "SDA_4") (pintype "input"))
      (node (ref "D9") (pin "2") (pinfunction "A_2") (pintype "unspecified"))
      (node (ref "Q9") (pin "2") (pinfunction "D_2") (pintype "unspecified"))
    )
    (net (code "9") (name "Net-(D1-A)") (class "Default")
      (node (ref "D1") (pin "2") (pinfunction "A_2") (pintype "unspecified"))
      (node (ref "Q1") (pin "2") (pinfunction "D_2") (pintype "unspecified"))
      (node (ref "VTB1") (pin "2") (pinfunction "FPI_2") (pintype "input"))
    )
    (net (code "10") (name "Net-(D2-A)") (class "Default")
      (node (ref "D2") (pin "2") (pinfunction "A_2") (pintype "unspecified"))
      (node (ref "Q2") (pin "2") (pinfunction "D_2") (pintype "unspecified"))
      (node (ref "VTB1") (pin "1") (pinfunction "FPO_1") (pintype "input"))
    )
    (net (code "11") (name "Net-(D3-A)") (class "Default")
      (node (ref "D3") (pin "2") (pinfunction "A_2") (pintype "unspecified"))
      (node (ref "Q3") (pin "2") (pinfunction "D_2") (pintype "unspecified"))
      (node (ref "VTB1") (pin "4") (pinfunction "FDI_4") (pintype "input"))
    )
    (net (code "12") (name "Net-(D4-A)") (class "Default")
      (node (ref "D4") (pin "2") (pinfunction "A_2") (pintype "unspecified"))
      (node (ref "Q4") (pin "2") (pinfunction "D_2") (pintype "unspecified"))
      (node (ref "VTA1") (pin "2") (pinfunction "FDO_2") (pintype "unspecified"))
    )
    (net (code "13") (name "Net-(D5-A)") (class "Default")
      (node (ref "D5") (pin "2") (pinfunction "A_2") (pintype "unspecified"))
      (node (ref "Q5") (pin "2") (pinfunction "D_2") (pintype "unspecified"))
      (node (ref "VTB1") (pin "6") (pinfunction "RDO_6") (pintype "input"))
    )
    (net (code "14") (name "Net-(D6-A)") (class "Default")
      (node (ref "D6") (pin "2") (pinfunction "A_2") (pintype "unspecified"))
      (node (ref "Q6") (pin "2") (pinfunction "D_2") (pintype "unspecified"))
      (node (ref "VTB1") (pin "5") (pinfunction "RDI_5") (pintype "input"))
    )
    (net (code "15") (name "Net-(D7-A)") (class "Default")
      (node (ref "D7") (pin "2") (pinfunction "A_2") (pintype "unspecified"))
      (node (ref "Q7") (pin "2") (pinfunction "D_2") (pintype "unspecified"))
      (node (ref "VTA1") (pin "3") (pinfunction "RPO_3") (pintype "unspecified"))
    )
    (net (code "16") (name "Net-(D8-A)") (class "Default")
      (node (ref "D8") (pin "2") (pinfunction "A_2") (pintype "unspecified"))
      (node (ref "Q8") (pin "2") (pinfunction "D_2") (pintype "unspecified"))
      (node (ref "VTB1") (pin "3") (pinfunction "RPI_3") (pintype "input"))
    )
    (net (code "17") (name "Net-(D15-C)") (class "Default")
      (node (ref "D15") (pin "1") (pinfunction "C_1") (pintype "unspecified"))
      (node (ref "D16") (pin "1") (pinfunction "C_1") (pintype "unspecified"))
      (node (ref "R38") (pin "2") (pinfunction "2_2") (pintype "unspecified"))
    )
    (net (code "18") (name "Net-(FD_LEVEL2-SIG)") (class "Default")
      (node (ref "FD_LEVEL2") (pin "2") (pinfunction "SIG_2") (pintype "input"))
      (node (ref "U4") (pin "6") (pinfunction "AIN2_6") (pintype "input"))
    )
    (net (code "19") (name "Net-(FD_PRESS1-SIG)") (class "Default")
      (node (ref "FD_PRESS1") (pin "2") (pinfunction "SIG_2") (pintype "input"))
      (node (ref "U5") (pin "6") (pinfunction "AIN2_6") (pintype "input"))
    )
    (net (code "20") (name "Net-(FP_LEVEL2-SIG)") (class "Default")
      (node (ref "FP_LEVEL2") (pin "2") (pinfunction "SIG_2") (pintype "input"))
      (node (ref "U4") (pin "4") (pinfunction "AIN0_4") (pintype "input"))
    )
    (net (code "21") (name "Net-(FP_PRESS1-SIG)") (class "Default")
      (node (ref "FP_PRESS1") (pin "2") (pinfunction "SIG_2") (pintype "input"))
      (node (ref "U5") (pin "4") (pinfunction "AIN0_4") (pintype "input"))
    )
    (net (code "22") (name "Net-(GPS-SCL)") (class "Default")
      (node (ref "GPS") (pin "3") (pinfunction "SCL_3") (pintype "input"))
      (node (ref "OLED1") (pin "3") (pinfunction "SCL_3") (pintype "input"))
      (node (ref "Q13") (pin "2") (pinfunction "S_2") (pintype "unspecified"))
      (node (ref "R28") (pin "1") (pinfunction "1_1") (pintype "input"))
      (node (ref "U8") (pin "2") (pinfunction "2_2") (pintype "unspecified"))
    )
    (net (code "23") (name "Net-(GPS-SDA)") (class "Default")
      (node (ref "GPS") (pin "4") (pinfunction "SDA_4") (pintype "input"))
      (node (ref "OLED1") (pin "4") (pinfunction "SDA_4") (pintype "input"))
      (node (ref "Q12") (pin "2") (pinfunction "S_2") (pintype "unspecified"))
      (node (ref "R30") (pin "1") (pinfunction "1_1") (pintype "input"))
      (node (ref "U8") (pin "5") (pinfunction "5_5") (pintype "unspecified"))
    )
    (net (code "24") (name "Net-(Q1-G)") (class "Default")
      (node (ref "Q1") (pin "1") (pinfunction "G_1") (pintype "unspecified"))
      (node (ref "R1") (pin "1") (pinfunction "1_1") (pintype "input"))
      (node (ref "R9") (pin "1") (pinfunction "1_1") (pintype "unspecified"))
    )
    (net (code "25") (name "Net-(Q2-G)") (class "Default")
      (node (ref "Q2") (pin "1") (pinfunction "G_1") (pintype "unspecified"))
      (node (ref "R10") (pin "1") (pinfunction "1_1") (pintype "unspecified"))
      (node (ref "R2") (pin "1") (pinfunction "1_1") (pintype "input"))
    )
    (net (code "26") (name "Net-(Q3-G)") (class "Default")
      (node (ref "Q3") (pin "1") (pinfunction "G_1") (pintype "unspecified"))
      (node (ref "R11") (pin "1") (pinfunction "1_1") (pintype "unspecified"))
      (node (ref "R3") (pin "1") (pinfunction "1_1") (pintype "input"))
    )
    (net (code "27") (name "Net-(Q4-G)") (class "Default")
      (node (ref "Q4") (pin "1") (pinfunction "G_1") (pintype "unspecified"))
      (node (ref "R12") (pin "1") (pinfunction "1_1") (pintype "unspecified"))
      (node (ref "R4") (pin "1") (pinfunction "1_1") (pintype "input"))
    )
    (net (code "28") (name "Net-(Q5-G)") (class "Default")
      (node (ref "Q5") (pin "1") (pinfunction "G_1") (pintype "unspecified"))
      (node (ref "R13") (pin "1") (pinfunction "1_1") (pintype "unspecified"))
      (node (ref "R5") (pin "1") (pinfunction "1_1") (pintype "input"))
    )
    (net (code "29") (name "Net-(Q6-G)") (class "Default")
      (node (ref "Q6") (pin "1") (pinfunction "G_1") (pintype "unspecified"))
      (node (ref "R14") (pin "1") (pinfunction "1_1") (pintype "unspecified"))
      (node (ref "R6") (pin "1") (pinfunction "1_1") (pintype "input"))
    )
    (net (code "30") (name "Net-(Q7-G)") (class "Default")
      (node (ref "Q7") (pin "1") (pinfunction "G_1") (pintype "unspecified"))
      (node (ref "R15") (pin "1") (pinfunction "1_1") (pintype "unspecified"))
      (node (ref "R7") (pin "1") (pinfunction "1_1") (pintype "input"))
    )
    (net (code "31") (name "Net-(Q8-G)") (class "Default")
      (node (ref "Q8") (pin "1") (pinfunction "G_1") (pintype "unspecified"))
      (node (ref "R16") (pin "1") (pinfunction "1_1") (pintype "unspecified"))
      (node (ref "R8") (pin "1") (pinfunction "1_1") (pintype "input"))
    )
    (net (code "32") (name "Net-(Q9-G)") (class "Default")
      (node (ref "Q9") (pin "1") (pinfunction "G_1") (pintype "unspecified"))
      (node (ref "R17") (pin "1") (pinfunction "1_1") (pintype "unspecified"))
      (node (ref "R18") (pin "1") (pinfunction "1_1") (pintype "input"))
    )
    (net (code "33") (name "Net-(Q11-D)") (class "Default")
      (node (ref "Q11") (pin "2") (pinfunction "D_2") (pintype "unspecified"))
      (node (ref "R25") (pin "1") (pinfunction "1_1") (pintype "input"))
      (node (ref "U7") (pin "11") (pinfunction "11_11") (pintype "unspecified"))
    )
    (net (code "34") (name "Net-(Q11-G)") (class "Default")
      (node (ref "Q11") (pin "1") (pinfunction "G_1") (pintype "unspecified"))
      (node (ref "R22") (pin "1") (pinfunction "1_1") (pintype "unspecified"))
      (node (ref "R23") (pin "1") (pinfunction "1_1") (pintype "input"))
    )
    (net (code "35") (name "Net-(Q12-D)") (class "Default")
      (node (ref "Q12") (pin "3") (pinfunction "D_3") (pintype "unspecified"))
      (node (ref "R27") (pin "2") (pinfunction "2_2") (pintype "input"))
      (node (ref "R42") (pin "2") (pinfunction "2_2") (pintype "input"))
      (node (ref "R44") (pin "1") (pinfunction "1_1") (pintype "input"))
      (node (ref "U4") (pin "9") (pinfunction "SDA_9") (pintype "bidirectional"))
      (node (ref "U5") (pin "9") (pinfunction "SDA_9") (pintype "bidirectional"))
    )
    (net (code "36") (name "Net-(Q13-D)") (class "Default")
      (node (ref "Q13") (pin "3") (pinfunction "D_3") (pintype "unspecified"))
      (node (ref "R29") (pin "1") (pinfunction "1_1") (pintype "input"))
      (node (ref "R33") (pin "2") (pinfunction "2_2") (pintype "input"))
      (node (ref "R45") (pin "1") (pinfunction "1_1") (pintype "input"))
      (node (ref "U4") (pin "10") (pinfunction "SCL_10") (pintype "input"))
      (node (ref "U5") (pin "10") (pinfunction "SCL_10") (pintype "input"))
    )
    (net (code "37") (name "Net-(Q14-D)") (class "Default")
      (node (ref "Q14") (pin "2") (pinfunction "D_2") (pintype "unspecified"))
      (node (ref "R40") (pin "1") (pinfunction "1_1") (pintype "input"))
    )
    (net (code "38") (name "Net-(Q14-G)") (class "Default")
      (node (ref "Q14") (pin "1") (pinfunction "G_1") (pintype "unspecified"))
      (node (ref "R37") (pin "1") (pinfunction "1_1") (pintype "input"))
      (node (ref "R38") (pin "1") (pinfunction "1_1") (pintype "unspecified"))
    )
    (net (code "39") (name "Net-(Q15-G)") (class "Default")
      (node (ref "Q15") (pin "1") (pinfunction "G_1") (pintype "unspecified"))
      (node (ref "R39") (pin "2") (pinfunction "2_2") (pintype "input"))
      (node (ref "R40") (pin "2") (pinfunction "2_2") (pintype "input"))
    )
    (net (code "40") (name "Net-(R9-Pad2)") (class "Default")
      (node (ref "R9") (pin "2") (pinfunction "2_2") (pintype "unspecified"))
      (node (ref "U7") (pin "7") (pinfunction "7_7") (pintype "unspecified"))
    )
    (net (code "41") (name "Net-(R10-Pad2)") (class "Default")
      (node (ref "R10") (pin "2") (pinfunction "2_2") (pintype "unspecified"))
      (node (ref "U7") (pin "8") (pinfunction "8_8") (pintype "unspecified"))
    )
    (net (code "42") (name "Net-(R11-Pad2)") (class "Default")
      (node (ref "R11") (pin "2") (pinfunction "2_2") (pintype "unspecified"))
      (node (ref "U7") (pin "9") (pinfunction "9_9") (pintype "unspecified"))
    )
    (net (code "43") (name "Net-(R12-Pad2)") (class "Default")
      (node (ref "R12") (pin "2") (pinfunction "2_2") (pintype "unspecified"))
      (node (ref "U7") (pin "10") (pinfunction "10_10") (pintype "unspecified"))
    )
    (net (code "44") (name "Net-(R13-Pad2)") (class "Default")
      (node (ref "R13") (pin "2") (pinfunction "2_2") (pintype "unspecified"))
      (node (ref "U8") (pin "9") (pinfunction "9_9") (pintype "unspecified"))
    )
    (net (code "45") (name "Net-(R14-Pad2)") (class "Default")
      (node (ref "R14") (pin "2") (pinfunction "2_2") (pintype "unspecified"))
      (node (ref "U8") (pin "7") (pinfunction "7_7") (pintype "unspecified"))
    )
    (net (code "46") (name "Net-(R15-Pad2)") (class "Default")
      (node (ref "R15") (pin "2") (pinfunction "2_2") (pintype "unspecified"))
      (node (ref "U8") (pin "6") (pinfunction "6_6") (pintype "unspecified"))
    )
    (net (code "47") (name "Net-(R16-Pad2)") (class "Default")
      (node (ref "R16") (pin "2") (pinfunction "2_2") (pintype "unspecified"))
      (node (ref "U8") (pin "1") (pinfunction "1_1") (pintype "unspecified"))
    )
    (net (code "48") (name "Net-(R17-Pad2)") (class "Default")
      (node (ref "R17") (pin "2") (pinfunction "2_2") (pintype "unspecified"))
      (node (ref "U7") (pin "13") (pinfunction "13_13") (pintype "unspecified"))
    )
    (net (code "49") (name "Net-(R19-Pad1)") (class "Default")
      (node (ref "R19") (pin "1") (pinfunction "1_1") (pintype "unspecified"))
      (node (ref "R24") (pin "2") (pinfunction "2_2") (pintype "unspecified"))
      (node (ref "U7") (pin "6") (pinfunction "6_6") (pintype "unspecified"))
    )
    (net (code "50") (name "Net-(RD_LEVEL2-SIG)") (class "Default")
      (node (ref "RD_LEVEL2") (pin "2") (pinfunction "SIG_2") (pintype "input"))
      (node (ref "U4") (pin "5") (pinfunction "AIN1_5") (pintype "input"))
    )
    (net (code "51") (name "Net-(RD_PRESS1-SIG)") (class "Default")
      (node (ref "RD_PRESS1") (pin "2") (pinfunction "SIG_2") (pintype "input"))
      (node (ref "U5") (pin "5") (pinfunction "AIN1_5") (pintype "input"))
    )
    (net (code "52") (name "Net-(RP_LEVEL2-SIG)") (class "Default")
      (node (ref "RP_LEVEL2") (pin "2") (pinfunction "SIG_2") (pintype "input"))
      (node (ref "U4") (pin "7") (pinfunction "AIN3_7") (pintype "input"))
    )
    (net (code "53") (name "Net-(RP_PRESS1-SIG)") (class "Default")
      (node (ref "RP_PRESS1") (pin "2") (pinfunction "SIG_2") (pintype "input"))
      (node (ref "U5") (pin "7") (pinfunction "AIN3_7") (pintype "input"))
    )
    (net (code "54") (name "Net-(TANK1-SIG)") (class "Default")
      (node (ref "R19") (pin "2") (pinfunction "2_2") (pintype "unspecified"))
      (node (ref "TANK1") (pin "2") (pinfunction "SIG_2") (pintype "input"))
    )
    (net (code "55") (name "Net-(U4-ALERT{slash}RDY)") (class "Default")
      (node (ref "R41") (pin "2") (pinfunction "2_2") (pintype "input"))
      (node (ref "U4") (pin "2") (pinfunction "ALERT/RDY_2") (pintype "output"))
    )
    (net (code "56") (name "Net-(U4-GND)") (class "Default")
      (node (ref "C1") (pin "2") (pinfunction "2_2") (pintype "unspecified"))
      (node (ref "U10") (pin "2") (pinfunction "2_2") (pintype "input"))
      (node (ref "U4") (pin "3") (pinfunction "GND_3") (pintype "unspecified"))
    )
    (net (code "57") (name "Net-(U4-VDD)") (class "Default")
      (node (ref "C1") (pin "1") (pinfunction "1_1") (pintype "unspecified"))
      (node (ref "R33") (pin "1") (pinfunction "1_1") (pintype "input"))
      (node (ref "R41") (pin "1") (pinfunction "1_1") (pintype "input"))
      (node (ref "R42") (pin "1") (pinfunction "1_1") (pintype "input"))
      (node (ref "U4") (pin "8") (pinfunction "VDD_8") (pintype "unspecified"))
      (node (ref "U9") (pin "2") (pinfunction "2_2") (pintype "input"))
    )
    (net (code "58") (name "Net-(U5-ALERT{slash}RDY)") (class "Default")
      (node (ref "R43") (pin "2") (pinfunction "2_2") (pintype "input"))
      (node (ref "U5") (pin "2") (pinfunction "ALERT/RDY_2") (pintype "output"))
    )
    (net (code "59") (name "Net-(U5-GND)") (class "Default")
      (node (ref "C2") (pin "2") (pinfunction "2_2") (pintype "unspecified"))
      (node (ref "U12") (pin "2") (pinfunction "2_2") (pintype "input"))
      (node (ref "U5") (pin "3") (pinfunction "GND_3") (pintype "unspecified"))
    )
    (net (code "60") (name "Net-(U5-VDD)") (class "Default")
      (node (ref "C2") (pin "1") (pinfunction "1_1") (pintype "unspecified"))
      (node (ref "R43") (pin "1") (pinfunction "1_1") (pintype "input"))
      (node (ref "R44") (pin "2") (pinfunction "2_2") (pintype "input"))
      (node (ref "R45") (pin "2") (pinfunction "2_2") (pintype "input"))
      (node (ref "U11") (pin "2") (pinfunction "2_2") (pintype "input"))
      (node (ref "U5") (pin "8") (pinfunction "VDD_8") (pintype "unspecified"))
    )
    (net (code "61") (name "Net-(U13-SW)") (class "Default")
      (node (ref "C12") (pin "2") (pinfunction "2_2") (pintype "input"))
      (node (ref "L3") (pin "1") (pinfunction "1_1") (pintype "unspecified"))
      (node (ref "U13") (pin "2") (pinfunction "SW_2") (pintype "unspecified"))
    )
    (net (code "62") (name "Net-(U13-VBST)") (class "Default")
      (node (ref "C12") (pin "1") (pinfunction "1_1") (pintype "input"))
      (node (ref "U13") (pin "6") (pinfunction "VBST_6") (pintype "unspecified"))
    )
    (net (code "63") (name "Net-(U13-VFB)") (class "Default")
      (node (ref "R50") (pin "1") (pinfunction "1_1") (pintype "input"))
      (node (ref "R51") (pin "2") (pinfunction "2_2") (pintype "input"))
      (node (ref "U13") (pin "4") (pinfunction "VFB_4") (pintype "unspecified"))
    )
    (net (code "64") (name "VCC") (class "Default")
      (node (ref "CN1") (pin "2") (pinfunction "GND_2") (pintype "input"))
      (node (ref "D10") (pin "1") (pinfunction "C_1") (pintype "unspecified"))
      (node (ref "Q15") (pin "3") (pinfunction "S_3") (pintype "unspecified"))
      (node (ref "R39") (pin "1") (pinfunction "1_1") (pintype "input"))
    )
    (net (code "65") (name "unconnected-(U7-Pad1)") (class "Default")
      (node (ref "U7") (pin "1") (pinfunction "1_1") (pintype "unspecified+no_connect"))
    )
    (net (code "66") (name "unconnected-(U7-Pad2)") (class "Default")
      (node (ref "U7") (pin "2") (pinfunction "2_2") (pintype "unspecified+no_connect"))
    )
    (net (code "67") (name "unconnected-(U7-Pad3)") (class "Default")
      (node (ref "U7") (pin "3") (pinfunction "3_3") (pintype "unspecified+no_connect"))
    )
    (net (code "68") (name "unconnected-(U7-Pad4)") (class "Default")
      (node (ref "U7") (pin "4") (pinfunction "4_4") (pintype "unspecified+no_connect"))
    )
    (net (code "69") (name "unconnected-(U7-Pad5)") (class "Default")
      (node (ref "U7") (pin "5") (pinfunction "5_5") (pintype "unspecified+no_connect"))
    )
    (net (code "70") (name "unconnected-(U8-Pad3)") (class "Default")
      (node (ref "U8") (pin "3") (pinfunction "3_3") (pintype "unspecified+no_connect"))
    )
    (net (code "71") (name "unconnected-(U8-Pad4)") (class "Default")
      (node (ref "U8") (pin "4") (pinfunction "4_4") (pintype "unspecified+no_connect"))
    )
    (net (code "72") (name "unconnected-(U8-Pad8)") (class "Default")
      (node (ref "U8") (pin "8") (pinfunction "8_8") (pintype "unspecified+no_connect"))
    )
    (net (code "73") (name "unconnected-(U8-Pad10)") (class "Default")
      (node (ref "U8") (pin "10") (pinfunction "10_10") (pintype "unspecified+no_connect"))
    )
    (net (code "74") (name "unconnected-(U8-Pad11)") (class "Default")
      (node (ref "U8") (pin "11") (pinfunction "11_11") (pintype "unspecified+no_connect"))
    )
    (net (code "75") (name "unconnected-(U8-Pad12)") (class "Default")
      (node (ref "U8") (pin "12") (pinfunction "12_12") (pintype "unspecified+no_connect"))
    )
    (net (code "76") (name "unconnected-(U8-Pad13)") (class "Default")
      (node (ref "U8") (pin "13") (pinfunction "13_13") (pintype "unspecified+no_connect"))
    )
  )
)
